# mpu6050.net
KiCad netlist of a schematic drawn in Altium Designer
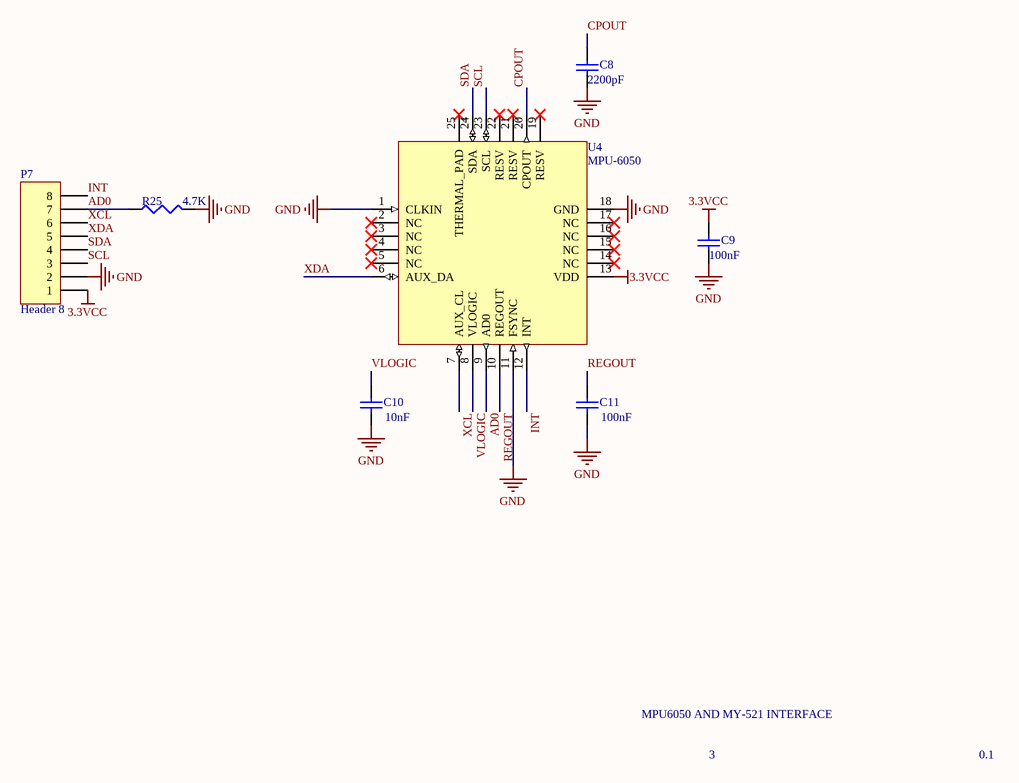
[diagram p0: mpu6050.SchDoc]

(export (version "E")
  (design (tool "Eeschema 10.0.6"))
  (components
    (comp (ref "C8")
      (value "2200pF")
      (footprint "C1206")
      (description "Capacitor (Semiconductor SIM Model)")
      (fields (field (name "Comment") "Cap Semi") (field (name "PUBLISHER") "Altium Limited"))
      (libsource (lib "Miscellaneous Devices") (part "Cap Semi"))
    )
    (comp (ref "C9")
      (value "100nF")
      (footprint "C1206")
      (description "Capacitor (Semiconductor SIM Model)")
      (fields (field (name "Comment") "Cap Semi") (field (name "PUBLISHER") "Altium Limited"))
      (libsource (lib "Miscellaneous Devices") (part "Cap Semi"))
    )
    (comp (ref "C10")
      (value "10nF")
      (footprint "C1206")
      (description "Capacitor (Semiconductor SIM Model)")
      (fields (field (name "Comment") "Cap Semi") (field (name "PUBLISHER") "Altium Limited"))
      (libsource (lib "Miscellaneous Devices") (part "Cap Semi"))
    )
    (comp (ref "C11")
      (value "100nF")
      (footprint "C1206")
      (description "Capacitor (Semiconductor SIM Model)")
      (fields (field (name "Comment") "Cap Semi") (field (name "PUBLISHER") "Altium Limited"))
      (libsource (lib "Miscellaneous Devices") (part "Cap Semi"))
    )
    (comp (ref "P7")
      (value "Header 8")
      (footprint "HDR1X8")
      (description "Header, 8-Pin")
      (fields (field (name "PUBLISHER") "Altium Limited"))
      (libsource (lib "Miscellaneous Connectors") (part "Header 8"))
    )
    (comp (ref "R25")
      (value "4.7K")
      (footprint "J1-0603")
      (description "Resistor")
      (fields (field (name "Comment") "Res3") (field (name "PUBLISHER") "Altium Limited"))
      (libsource (lib "Miscellaneous Devices") (part "Res3"))
    )
    (comp (ref "U4")
      (value "MPU-6050")
      (footprint "QFN50P400X400X95-25N")
      (description "INVENSENSE - Módulo MEMS, Giroscopio de Tres Ejes, Acelerómetro de Tres Ejes")
      (fields (field (name "MANUFACTURER") "TDK InvenSense"))
      (libsource (lib "ecubelib") (part "MPU-6050"))
    )
  )
  (nets
    (net (code "1") (name "/AD0") (class "Default")
      (node (ref "P7") (pin "7") (pinfunction "7_7") (pintype "passive"))
      (node (ref "R25") (pin "1") (pinfunction "1_1") (pintype "passive"))
      (node (ref "U4") (pin "9") (pinfunction "AD0_9") (pintype "output"))
    )
    (net (code "2") (name "/CPOUT") (class "Default")
      (node (ref "C8") (pin "2") (pinfunction "2_2") (pintype "passive"))
      (node (ref "U4") (pin "20") (pinfunction "CPOUT_20") (pintype "output"))
    )
    (net (code "3") (name "/INT") (class "Default")
      (node (ref "P7") (pin "8") (pinfunction "8_8") (pintype "passive"))
      (node (ref "U4") (pin "12") (pinfunction "INT_12") (pintype "output"))
    )
    (net (code "4") (name "/REGOUT") (class "Default")
      (node (ref "C11") (pin "2") (pinfunction "2_2") (pintype "passive"))
      (node (ref "U4") (pin "10") (pinfunction "REGOUT_10") (pintype "passive"))
    )
    (net (code "5") (name "/SCL") (class "Default")
      (node (ref "P7") (pin "3") (pinfunction "3_3") (pintype "passive"))
      (node (ref "U4") (pin "23") (pinfunction "SCL_23") (pintype "bidirectional"))
    )
    (net (code "6") (name "/SDA") (class "Default")
      (node (ref "P7") (pin "4") (pinfunction "4_4") (pintype "passive"))
      (node (ref "U4") (pin "24") (pinfunction "SDA_24") (pintype "bidirectional"))
    )
    (net (code "7") (name "/VLOGIC") (class "Default")
      (node (ref "C10") (pin "2") (pinfunction "2_2") (pintype "passive"))
      (node (ref "U4") (pin "8") (pinfunction "VLOGIC_8") (pintype "power_in"))
    )
    (net (code "8") (name "/XCL") (class "Default")
      (node (ref "P7") (pin "6") (pinfunction "6_6") (pintype "passive"))
      (node (ref "U4") (pin "7") (pinfunction "AUX_CL_7") (pintype "bidirectional"))
    )
    (net (code "9") (name "/XDA") (class "Default")
      (node (ref "P7") (pin "5") (pinfunction "5_5") (pintype "passive"))
      (node (ref "U4") (pin "6") (pinfunction "AUX_DA_6") (pintype "bidirectional"))
    )
    (net (code "10") (name "3.3VCC") (class "Default")
      (node (ref "C9") (pin "2") (pinfunction "2_2") (pintype "passive"))
      (node (ref "P7") (pin "1") (pinfunction "1_1") (pintype "passive"))
      (node (ref "U4") (pin "13") (pinfunction "VDD_13") (pintype "power_in"))
    )
    (net (code "11") (name "GND") (class "Default")
      (node (ref "C10") (pin "1") (pinfunction "1_1") (pintype "passive"))
      (node (ref "C11") (pin "1") (pinfunction "1_1") (pintype "passive"))
      (node (ref "C8") (pin "1") (pinfunction "1_1") (pintype "passive"))
      (node (ref "C9") (pin "1") (pinfunction "1_1") (pintype "passive"))
      (node (ref "P7") (pin "2") (pinfunction "2_2") (pintype "passive"))
      (node (ref "R25") (pin "2") (pinfunction "2_2") (pintype "passive"))
      (node (ref "U4") (pin "1") (pinfunction "CLKIN_1") (pintype "input"))
      (node (ref "U4") (pin "11") (pinfunction "FSYNC_11") (pintype "input"))
      (node (ref "U4") (pin "18") (pinfunction "GND_18") (pintype "power_in"))
    )
    (net (code "12") (name "unconnected-(U4-NC-Pad2)") (class "Default")
      (node (ref "U4") (pin "2") (pinfunction "NC_2") (pintype "passive+no_connect"))
    )
    (net (code "13") (name "unconnected-(U4-NC-Pad3)") (class "Default")
      (node (ref "U4") (pin "3") (pinfunction "NC_3") (pintype "passive+no_connect"))
    )
    (net (code "14") (name "unconnected-(U4-NC-Pad4)") (class "Default")
      (node (ref "U4") (pin "4") (pinfunction "NC_4") (pintype "passive+no_connect"))
    )
    (net (code "15") (name "unconnected-(U4-NC-Pad5)") (class "Default")
      (node (ref "U4") (pin "5") (pinfunction "NC_5") (pintype "passive+no_connect"))
    )
    (net (code "16") (name "unconnected-(U4-NC-Pad14)") (class "Default")
      (node (ref "U4") (pin "14") (pinfunction "NC_14") (pintype "passive+no_connect"))
    )
    (net (code "17") (name "unconnected-(U4-NC-Pad15)") (class "Default")
      (node (ref "U4") (pin "15") (pinfunction "NC_15") (pintype "passive+no_connect"))
    )
    (net (code "18") (name "unconnected-(U4-NC-Pad16)") (class "Default")
      (node (ref "U4") (pin "16") (pinfunction "NC_16") (pintype "passive+no_connect"))
    )
    (net (code "19") (name "unconnected-(U4-NC-Pad17)") (class "Default")
      (node (ref "U4") (pin "17") (pinfunction "NC_17") (pintype "passive+no_connect"))
    )
    (net (code "20") (name "unconnected-(U4-RESV-Pad19)") (class "Default")
      (node (ref "U4") (pin "19") (pinfunction "RESV_19") (pintype "passive+no_connect"))
    )
    (net (code "21") (name "unconnected-(U4-RESV-Pad21)") (class "Default")
      (node (ref "U4") (pin "21") (pinfunction "RESV_21") (pintype "passive+no_connect"))
    )
    (net (code "22") (name "unconnected-(U4-RESV-Pad22)") (class "Default")
      (node (ref "U4") (pin "22") (pinfunction "RESV_22") (pintype "passive+no_connect"))
    )
    (net (code "23") (name "unconnected-(U4-THERMAL_PAD-Pad25)") (class "Default")
      (node (ref "U4") (pin "25") (pinfunction "THERMAL_PAD_25") (pintype "passive+no_connect"))
    )
  )
)
